# Ring_opto_interface_v1.net
KiCad netlist of a schematic drawn in EAGLE
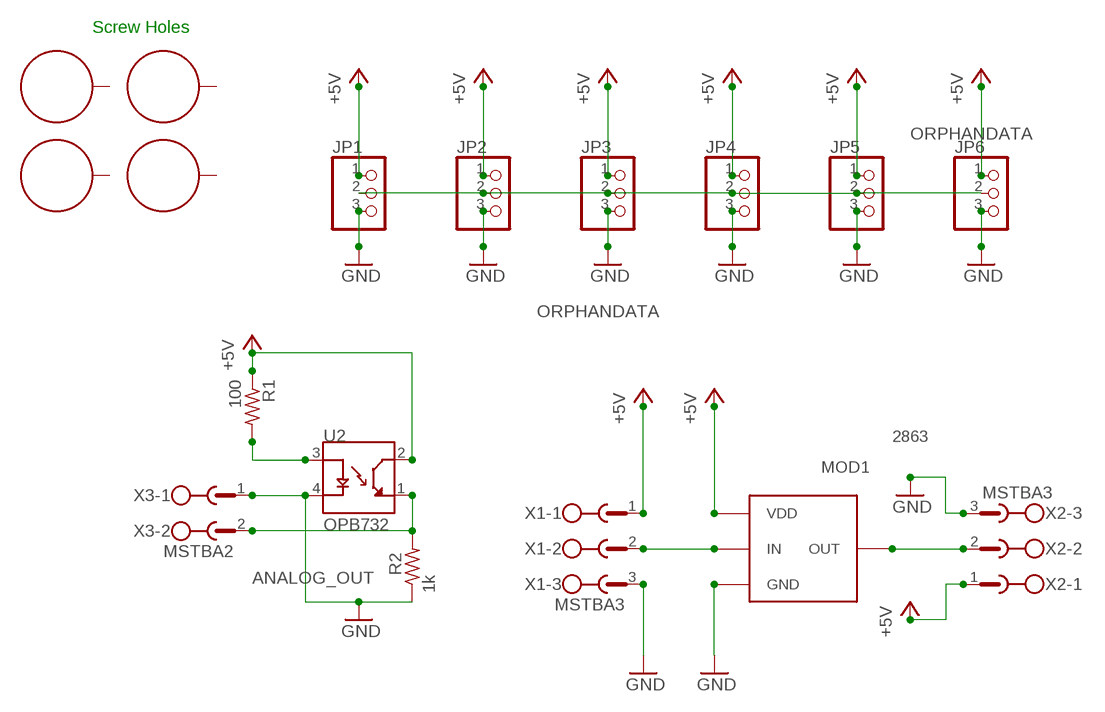
[diagram p0: schematic, sheet 1]

(export (version "E")
  (design (tool "Eeschema 10.0.6"))
  (components
    (comp (ref "H1")
      (value "STANDOFF_ELECTRICAL5-32")
      (footprint "eagle-import:STANDOFF_ELECTRICAL_5_32")
      (libsource (lib "eagle-import") (part "STANDOFF_ELECTRICAL5-32"))
    )
    (comp (ref "H2")
      (value "STANDOFF_ELECTRICAL5-32")
      (footprint "eagle-import:STANDOFF_ELECTRICAL_5_32")
      (libsource (lib "eagle-import") (part "STANDOFF_ELECTRICAL5-32"))
    )
    (comp (ref "H3")
      (value "STANDOFF_ELECTRICAL5-32")
      (footprint "eagle-import:STANDOFF_ELECTRICAL_5_32")
      (libsource (lib "eagle-import") (part "STANDOFF_ELECTRICAL5-32"))
    )
    (comp (ref "H4")
      (value "STANDOFF_ELECTRICAL5-32")
      (footprint "eagle-import:STANDOFF_ELECTRICAL_5_32")
      (libsource (lib "eagle-import") (part "STANDOFF_ELECTRICAL5-32"))
    )
    (comp (ref "JP1")
      (value "PINHD-1X3CB")
      (footprint "eagle-import:1X03-CLEANBIG")
      (libsource (lib "eagle-import") (part "PINHD-1X3CB"))
    )
    (comp (ref "JP2")
      (value "PINHD-1X3CB")
      (footprint "eagle-import:1X03-CLEANBIG")
      (libsource (lib "eagle-import") (part "PINHD-1X3CB"))
    )
    (comp (ref "JP3")
      (value "PINHD-1X3CB")
      (footprint "eagle-import:1X03-CLEANBIG")
      (libsource (lib "eagle-import") (part "PINHD-1X3CB"))
    )
    (comp (ref "JP4")
      (value "PINHD-1X3CB")
      (footprint "eagle-import:1X03-CLEANBIG")
      (libsource (lib "eagle-import") (part "PINHD-1X3CB"))
    )
    (comp (ref "JP5")
      (value "PINHD-1X3CB")
      (footprint "eagle-import:1X03-CLEANBIG")
      (libsource (lib "eagle-import") (part "PINHD-1X3CB"))
    )
    (comp (ref "JP6")
      (value "PINHD-1X3CB")
      (footprint "eagle-import:1X03-CLEANBIG")
      (libsource (lib "eagle-import") (part "PINHD-1X3CB"))
    )
    (comp (ref "MOD1")
      (value "2863")
      (footprint "eagle-import:ADAFRUIT_2863")
      (fields (field (name "MF") "Adafruit"))
      (libsource (lib "eagle-import") (part "2863"))
    )
    (comp (ref "R1")
      (value "100")
      (footprint "eagle-import:RESAD1176W63L850D250B")
      (libsource (lib "eagle-import") (part "R-USAXIAL-11.7MM-PITCH_"))
    )
    (comp (ref "R2")
      (value "1k")
      (footprint "eagle-import:RESAD1176W63L850D250B")
      (libsource (lib "eagle-import") (part "R-USAXIAL-11.7MM-PITCH_"))
    )
    (comp (ref "U2")
      (value "OPB732")
      (footprint "eagle-import:OPTO_OPB732")
      (fields (field (name "MF") "TT Electronics/Optek"))
      (libsource (lib "eagle-import") (part "OPB732"))
    )
    (comp (ref "X1")
      (value "MSTBA3")
      (footprint "eagle-import:MSTBA3")
      (fields (field (name "MF") "FARNELL") (field (name "MPN") "1757255"))
      (libsource (lib "eagle-import") (part "MSTBA3"))
    )
    (comp (ref "X2")
      (value "MSTBA3")
      (footprint "eagle-import:MSTBA3")
      (fields (field (name "MF") "FARNELL") (field (name "MPN") "1757255"))
      (libsource (lib "eagle-import") (part "MSTBA3"))
    )
    (comp (ref "X3")
      (value "MSTBA2")
      (footprint "eagle-import:MSTBA2")
      (fields (field (name "MF") "FARNELL") (field (name "MPN") "1757242"))
      (libsource (lib "eagle-import") (part "MSTBA2"))
    )
  )
  (nets
    (net (code "1") (name "+5V") (class "Default")
      (node (ref "JP1") (pin "1") (pinfunction "1_1") (pintype "passive"))
      (node (ref "JP2") (pin "1") (pinfunction "1_1") (pintype "passive"))
      (node (ref "JP3") (pin "1") (pinfunction "1_1") (pintype "passive"))
      (node (ref "JP4") (pin "1") (pinfunction "1_1") (pintype "passive"))
      (node (ref "JP5") (pin "1") (pinfunction "1_1") (pintype "passive"))
      (node (ref "JP6") (pin "1") (pinfunction "1_1") (pintype "passive"))
      (node (ref "MOD1") (pin "VDD1") (pinfunction "VDD_VDD1") (pintype "power_in"))
      (node (ref "MOD1") (pin "VDD2") (pinfunction "VDD_VDD2") (pintype "power_in"))
      (node (ref "R1") (pin "1") (pinfunction "1_1") (pintype "passive"))
      (node (ref "U2") (pin "2") (pinfunction "CT_2") (pintype "passive"))
      (node (ref "X1") (pin "1") (pinfunction "1_1") (pintype "passive"))
      (node (ref "X2") (pin "1") (pinfunction "1_1") (pintype "passive"))
    )
    (net (code "2") (name "/ANALOG_OUT") (class "Default")
      (node (ref "R2") (pin "2") (pinfunction "2_2") (pintype "passive"))
      (node (ref "U2") (pin "1") (pinfunction "ET_1") (pintype "passive"))
      (node (ref "X3") (pin "2") (pinfunction "1_2") (pintype "passive"))
    )
    (net (code "3") (name "/ORPHANDATA") (class "Default")
      (node (ref "JP1") (pin "2") (pinfunction "2_2") (pintype "passive"))
      (node (ref "JP2") (pin "2") (pinfunction "2_2") (pintype "passive"))
      (node (ref "JP3") (pin "2") (pinfunction "2_2") (pintype "passive"))
      (node (ref "JP4") (pin "2") (pinfunction "2_2") (pintype "passive"))
      (node (ref "JP5") (pin "2") (pinfunction "2_2") (pintype "passive"))
      (node (ref "JP6") (pin "2") (pinfunction "2_2") (pintype "passive"))
    )
    (net (code "4") (name "GND") (class "Default")
      (node (ref "JP1") (pin "3") (pinfunction "3_3") (pintype "passive"))
      (node (ref "JP2") (pin "3") (pinfunction "3_3") (pintype "passive"))
      (node (ref "JP3") (pin "3") (pinfunction "3_3") (pintype "passive"))
      (node (ref "JP4") (pin "3") (pinfunction "3_3") (pintype "passive"))
      (node (ref "JP5") (pin "3") (pinfunction "3_3") (pintype "passive"))
      (node (ref "JP6") (pin "3") (pinfunction "3_3") (pintype "passive"))
      (node (ref "MOD1") (pin "GND1") (pinfunction "GND_GND1") (pintype "power_in"))
      (node (ref "MOD1") (pin "GND2") (pinfunction "GND_GND2") (pintype "power_in"))
      (node (ref "R2") (pin "1") (pinfunction "1_1") (pintype "passive"))
      (node (ref "U2") (pin "4") (pinfunction "C_4") (pintype "passive"))
      (node (ref "X1") (pin "3") (pinfunction "1_3") (pintype "passive"))
      (node (ref "X2") (pin "3") (pinfunction "1_3") (pintype "passive"))
      (node (ref "X3") (pin "1") (pinfunction "1_1") (pintype "passive"))
    )
    (net (code "5") (name "Net-(U2-A)") (class "Default")
      (node (ref "R1") (pin "2") (pinfunction "2_2") (pintype "passive"))
      (node (ref "U2") (pin "3") (pinfunction "A_3") (pintype "passive"))
    )
    (net (code "6") (name "Net-(X1B-1)") (class "Default")
      (node (ref "MOD1") (pin "IN") (pinfunction "IN_IN") (pintype "input"))
      (node (ref "X1") (pin "2") (pinfunction "1_2") (pintype "passive"))
    )
    (net (code "7") (name "Net-(X2B-1)") (class "Default")
      (node (ref "MOD1") (pin "OUT") (pinfunction "OUT_OUT") (pintype "output"))
      (node (ref "X2") (pin "2") (pinfunction "1_2") (pintype "passive"))
    )
    (net (code "8") (name "unconnected-(H1-P$1-PadP1)") (class "Default")
      (node (ref "H1") (pin "P1") (pinfunction "P$1_P1") (pintype "bidirectional"))
    )
    (net (code "9") (name "unconnected-(H2-P$1-PadP1)") (class "Default")
      (node (ref "H2") (pin "P1") (pinfunction "P$1_P1") (pintype "bidirectional"))
    )
    (net (code "10") (name "unconnected-(H3-P$1-PadP1)") (class "Default")
      (node (ref "H3") (pin "P1") (pinfunction "P$1_P1") (pintype "bidirectional"))
    )
    (net (code "11") (name "unconnected-(H4-P$1-PadP1)") (class "Default")
      (node (ref "H4") (pin "P1") (pinfunction "P$1_P1") (pintype "bidirectional"))
    )
  )
)
